# dummy_load_schematic.net
KiCad netlist of a schematic drawn in EAGLE
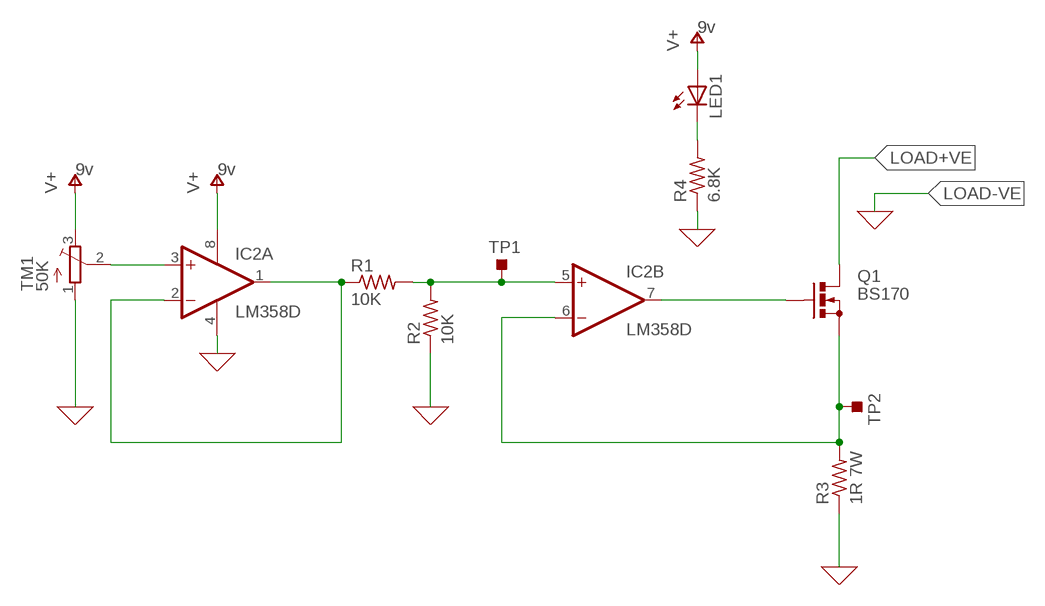
[diagram p0: schematic, sheet 1]

(export (version "E")
  (design (tool "Eeschema 10.0.6"))
  (components
    (comp (ref "IC1")
      (value "OP1277RM")
      (footprint "eagle-import:MSOP08")
      (libsource (lib "eagle-import") (part "OP1277RM"))
    )
    (comp (ref "IC2")
      (value "LM358D")
      (footprint "eagle-import:SO08")
      (libsource (lib "eagle-import") (part "LM358D"))
    )
    (comp (ref "LED1")
      (value "LED5MM")
      (footprint "eagle-import:LED5MM")
      (libsource (lib "eagle-import") (part "LED5MM"))
    )
    (comp (ref "Q1")
      (value "BS170")
      (footprint "eagle-import:SOT54E")
      (libsource (lib "eagle-import") (part "BS170"))
    )
    (comp (ref "R1")
      (value "10K")
      (footprint "eagle-import:0204V")
      (libsource (lib "eagle-import") (part "R-US_0204/2V"))
    )
    (comp (ref "R2")
      (value "10K")
      (footprint "eagle-import:0204V")
      (libsource (lib "eagle-import") (part "R-US_0204/2V"))
    )
    (comp (ref "R3")
      (value "1R 7W")
      (footprint "eagle-import:0204V")
      (libsource (lib "eagle-import") (part "R-US_0204/2V"))
    )
    (comp (ref "R4")
      (value "6.8K")
      (footprint "eagle-import:0204V")
      (libsource (lib "eagle-import") (part "R-US_0204/2V"))
    )
    (comp (ref "TM1")
      (value "50K")
      (footprint "eagle-import:TRIM-3386")
      (libsource (lib "eagle-import") (part "TRIMPOT3386"))
    )
    (comp (ref "TP1")
      (value "TESTPOINT_TPS-PAD-036")
      (footprint "eagle-import:TESTPOINT_PAD-036")
      (libsource (lib "eagle-import") (part "TESTPOINT_TPS-PAD-036"))
    )
    (comp (ref "TP2")
      (value "TESTPOINT_TPS-PAD-036")
      (footprint "eagle-import:TESTPOINT_PAD-036")
      (libsource (lib "eagle-import") (part "TESTPOINT_TPS-PAD-036"))
    )
  )
  (nets
    (net (code "1") (name "LOAD+VE") (class "Default")
      (node (ref "Q1") (pin "D") (pinfunction "D_D") (pintype "passive"))
    )
    (net (code "2") (name "LOAD-VE") (class "Default")
      (node (ref "IC1") (pin "4") (pinfunction "V-_4") (pintype "power_in"))
      (node (ref "R2") (pin "1") (pinfunction "1_1") (pintype "passive"))
      (node (ref "R3") (pin "1") (pinfunction "1_1") (pintype "passive"))
      (node (ref "R4") (pin "1") (pinfunction "1_1") (pintype "passive"))
      (node (ref "TM1") (pin "1") (pinfunction "A_1") (pintype "passive"))
    )
    (net (code "3") (name "Net-(IC2A-+IN)") (class "Default")
      (node (ref "IC2") (pin "3") (pinfunction "+IN_3") (pintype "input"))
      (node (ref "TM1") (pin "2") (pinfunction "S_2") (pintype "passive"))
    )
    (net (code "4") (name "Net-(IC2A--IN)") (class "Default")
      (node (ref "IC2") (pin "1") (pinfunction "OUT_1") (pintype "output"))
      (node (ref "IC2") (pin "2") (pinfunction "-IN_2") (pintype "input"))
      (node (ref "R1") (pin "1") (pinfunction "1_1") (pintype "passive"))
    )
    (net (code "5") (name "Net-(IC2B-+IN)") (class "Default")
      (node (ref "IC2") (pin "5") (pinfunction "+IN_5") (pintype "input"))
      (node (ref "R1") (pin "2") (pinfunction "2_2") (pintype "passive"))
      (node (ref "R2") (pin "2") (pinfunction "2_2") (pintype "passive"))
      (node (ref "TP1") (pin "1") (pinfunction "TP_1") (pintype "passive"))
    )
    (net (code "6") (name "Net-(IC2B--IN)") (class "Default")
      (node (ref "IC2") (pin "6") (pinfunction "-IN_6") (pintype "input"))
      (node (ref "Q1") (pin "S") (pinfunction "S_S") (pintype "passive"))
      (node (ref "R3") (pin "2") (pinfunction "2_2") (pintype "passive"))
      (node (ref "TP2") (pin "1") (pinfunction "TP_1") (pintype "passive"))
    )
    (net (code "7") (name "Net-(IC2B-OUT)") (class "Default")
      (node (ref "IC2") (pin "7") (pinfunction "OUT_7") (pintype "output"))
      (node (ref "Q1") (pin "G") (pinfunction "G_G") (pintype "passive"))
    )
    (net (code "8") (name "Net-(LED1-C)") (class "Default")
      (node (ref "LED1") (pin "K") (pinfunction "C_K") (pintype "passive"))
      (node (ref "R4") (pin "2") (pinfunction "2_2") (pintype "passive"))
    )
    (net (code "9") (name "V+") (class "Default")
      (node (ref "IC1") (pin "8") (pinfunction "V+_8") (pintype "power_in"))
      (node (ref "LED1") (pin "A") (pinfunction "A_A") (pintype "passive"))
      (node (ref "TM1") (pin "3") (pinfunction "E_3") (pintype "passive"))
    )
  )
)
